# main_board.net
KiCad netlist of a schematic drawn in EAGLE
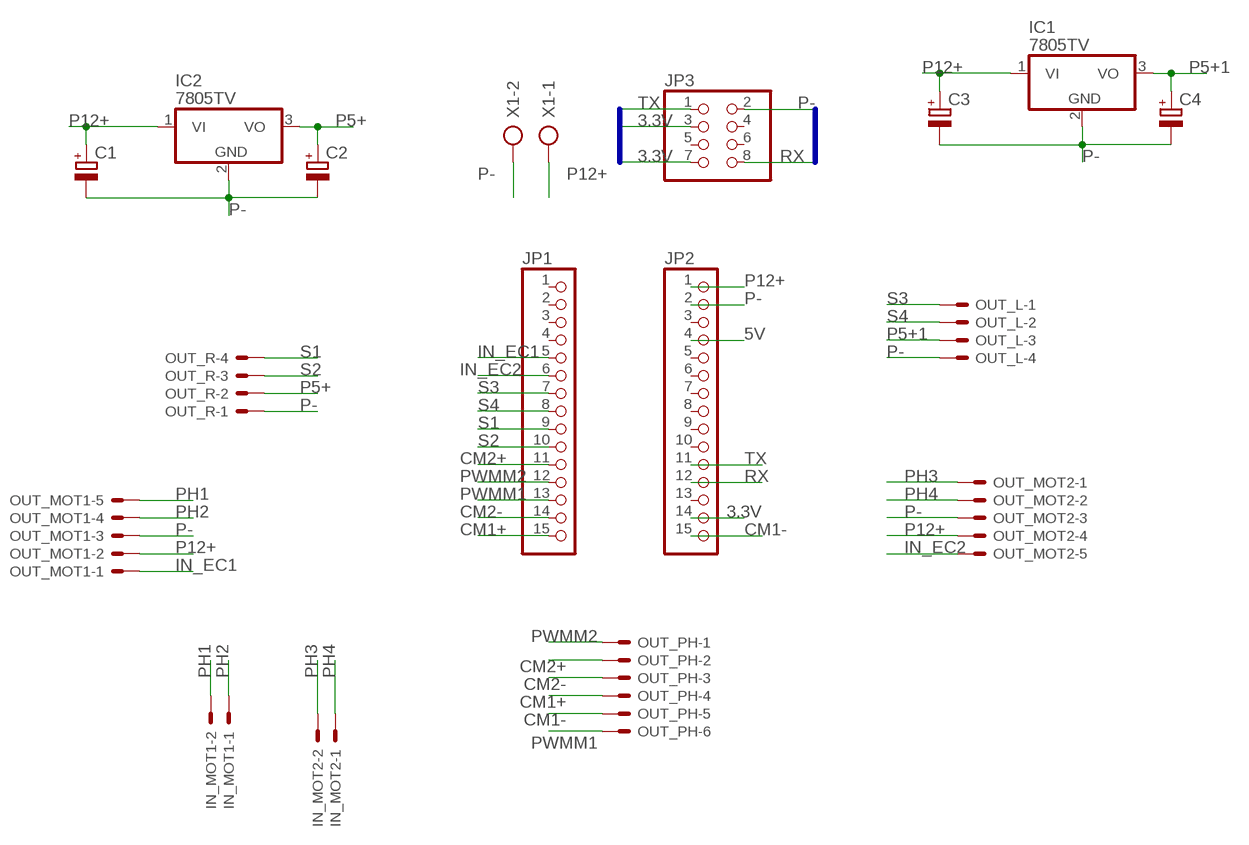
[diagram p0: schematic, sheet 1]

(export (version "E")
  (design (tool "Eeschema 10.0.6"))
  (components
    (comp (ref "C1")
      (value "CPOL-EUE3.5-10")
      (footprint "eagle-import:E3,5-10")
      (libsource (lib "eagle-import") (part "CPOL-EUE3.5-10"))
    )
    (comp (ref "C2")
      (value "CPOL-EUE3.5-10")
      (footprint "eagle-import:E3,5-10")
      (libsource (lib "eagle-import") (part "CPOL-EUE3.5-10"))
    )
    (comp (ref "C3")
      (value "CPOL-EUE3.5-10")
      (footprint "eagle-import:E3,5-10")
      (libsource (lib "eagle-import") (part "CPOL-EUE3.5-10"))
    )
    (comp (ref "C4")
      (value "CPOL-EUE3.5-10")
      (footprint "eagle-import:E3,5-10")
      (libsource (lib "eagle-import") (part "CPOL-EUE3.5-10"))
    )
    (comp (ref "IC1")
      (value "7805TV")
      (footprint "eagle-import:TO220V")
      (libsource (lib "eagle-import") (part "78TV05"))
    )
    (comp (ref "IC2")
      (value "7805TV")
      (footprint "eagle-import:TO220V")
      (libsource (lib "eagle-import") (part "78TV05"))
    )
    (comp (ref "IN_MOT1")
      (value "22-23-2021")
      (footprint "eagle-import:22-23-2021")
      (fields (field (name "MF") "MOLEX"))
      (libsource (lib "eagle-import") (part "22-23-2021"))
    )
    (comp (ref "IN_MOT2")
      (value "22-23-2021")
      (footprint "eagle-import:22-23-2021")
      (fields (field (name "MF") "MOLEX"))
      (libsource (lib "eagle-import") (part "22-23-2021"))
    )
    (comp (ref "JP1")
      (value "PINHD-1X15")
      (footprint "eagle-import:1X15")
      (libsource (lib "eagle-import") (part "PINHD-1X15"))
    )
    (comp (ref "JP2")
      (value "PINHD-1X15")
      (footprint "eagle-import:1X15")
      (libsource (lib "eagle-import") (part "PINHD-1X15"))
    )
    (comp (ref "JP3")
      (value "PINHD-2X4")
      (footprint "eagle-import:2X04")
      (libsource (lib "eagle-import") (part "PINHD-2X4"))
    )
    (comp (ref "OUT_L")
      (value "22-23-2041")
      (footprint "eagle-import:22-23-2041")
      (fields (field (name "MF") "MOLEX"))
      (libsource (lib "eagle-import") (part "22-23-2041"))
    )
    (comp (ref "OUT_MOT1")
      (value "22-23-2051")
      (footprint "eagle-import:22-23-2051")
      (fields (field (name "MF") "MOLEX"))
      (libsource (lib "eagle-import") (part "22-23-2051"))
    )
    (comp (ref "OUT_MOT2")
      (value "22-23-2051")
      (footprint "eagle-import:22-23-2051")
      (fields (field (name "MF") "MOLEX"))
      (libsource (lib "eagle-import") (part "22-23-2051"))
    )
    (comp (ref "OUT_PH")
      (value "22-23-2061")
      (footprint "eagle-import:22-23-2061")
      (fields (field (name "MF") "MOLEX"))
      (libsource (lib "eagle-import") (part "22-23-2061"))
    )
    (comp (ref "OUT_R")
      (value "22-23-2041")
      (footprint "eagle-import:22-23-2041")
      (fields (field (name "MF") "MOLEX"))
      (libsource (lib "eagle-import") (part "22-23-2041"))
    )
    (comp (ref "X1")
      (value "AK300/2")
      (footprint "eagle-import:AK300_2")
      (libsource (lib "eagle-import") (part "AK300/2"))
    )
  )
  (nets
    (net (code "1") (name "/3.3V") (class "Default")
      (node (ref "JP2") (pin "14") (pinfunction "14_14") (pintype "passive"))
      (node (ref "JP3") (pin "3") (pinfunction "3_3") (pintype "passive"))
      (node (ref "JP3") (pin "7") (pinfunction "7_7") (pintype "passive"))
    )
    (net (code "2") (name "/5V") (class "Default")
      (node (ref "JP2") (pin "4") (pinfunction "4_4") (pintype "passive"))
    )
    (net (code "3") (name "/CM1+") (class "Default")
      (node (ref "JP1") (pin "15") (pinfunction "15_15") (pintype "passive"))
      (node (ref "OUT_PH") (pin "4") (pinfunction "S_4") (pintype "passive"))
    )
    (net (code "4") (name "/CM1-") (class "Default")
      (node (ref "JP2") (pin "15") (pinfunction "15_15") (pintype "passive"))
      (node (ref "OUT_PH") (pin "5") (pinfunction "S_5") (pintype "passive"))
    )
    (net (code "5") (name "/CM2+") (class "Default")
      (node (ref "JP1") (pin "11") (pinfunction "11_11") (pintype "passive"))
      (node (ref "OUT_PH") (pin "2") (pinfunction "S_2") (pintype "passive"))
    )
    (net (code "6") (name "/CM2-") (class "Default")
      (node (ref "JP1") (pin "14") (pinfunction "14_14") (pintype "passive"))
      (node (ref "OUT_PH") (pin "3") (pinfunction "S_3") (pintype "passive"))
    )
    (net (code "7") (name "/IN_EC1") (class "Default")
      (node (ref "JP1") (pin "5") (pinfunction "5_5") (pintype "passive"))
      (node (ref "OUT_MOT1") (pin "1") (pinfunction "S_1") (pintype "passive"))
    )
    (net (code "8") (name "/IN_EC2") (class "Default")
      (node (ref "JP1") (pin "6") (pinfunction "6_6") (pintype "passive"))
      (node (ref "OUT_MOT2") (pin "5") (pinfunction "S_5") (pintype "passive"))
    )
    (net (code "9") (name "/P-") (class "Default")
      (node (ref "C1") (pin "-") (pinfunction "-_-") (pintype "passive"))
      (node (ref "C2") (pin "-") (pinfunction "-_-") (pintype "passive"))
      (node (ref "C3") (pin "-") (pinfunction "-_-") (pintype "passive"))
      (node (ref "C4") (pin "-") (pinfunction "-_-") (pintype "passive"))
      (node (ref "IC1") (pin "2") (pinfunction "GND_2") (pintype "passive"))
      (node (ref "IC2") (pin "2") (pinfunction "GND_2") (pintype "passive"))
      (node (ref "JP2") (pin "2") (pinfunction "2_2") (pintype "passive"))
      (node (ref "JP3") (pin "2") (pinfunction "2_2") (pintype "passive"))
      (node (ref "OUT_L") (pin "4") (pinfunction "S_4") (pintype "passive"))
      (node (ref "OUT_MOT1") (pin "3") (pinfunction "S_3") (pintype "passive"))
      (node (ref "OUT_MOT2") (pin "3") (pinfunction "S_3") (pintype "passive"))
      (node (ref "OUT_R") (pin "1") (pinfunction "S_1") (pintype "passive"))
      (node (ref "X1") (pin "2") (pinfunction "KL_2") (pintype "passive"))
    )
    (net (code "10") (name "/P5+") (class "Default")
      (node (ref "C2") (pin "+") (pinfunction "+_+") (pintype "passive"))
      (node (ref "IC2") (pin "3") (pinfunction "VO_3") (pintype "passive"))
      (node (ref "OUT_R") (pin "2") (pinfunction "S_2") (pintype "passive"))
    )
    (net (code "11") (name "/P5+1") (class "Default")
      (node (ref "C4") (pin "+") (pinfunction "+_+") (pintype "passive"))
      (node (ref "IC1") (pin "3") (pinfunction "VO_3") (pintype "passive"))
      (node (ref "OUT_L") (pin "3") (pinfunction "S_3") (pintype "passive"))
    )
    (net (code "12") (name "/P12+") (class "Default")
      (node (ref "C1") (pin "+") (pinfunction "+_+") (pintype "passive"))
      (node (ref "C3") (pin "+") (pinfunction "+_+") (pintype "passive"))
      (node (ref "IC1") (pin "1") (pinfunction "VI_1") (pintype "input"))
      (node (ref "IC2") (pin "1") (pinfunction "VI_1") (pintype "input"))
      (node (ref "JP2") (pin "1") (pinfunction "1_1") (pintype "passive"))
      (node (ref "OUT_MOT1") (pin "2") (pinfunction "S_2") (pintype "passive"))
      (node (ref "OUT_MOT2") (pin "4") (pinfunction "S_4") (pintype "passive"))
      (node (ref "X1") (pin "1") (pinfunction "KL_1") (pintype "passive"))
    )
    (net (code "13") (name "/PH1") (class "Default")
      (node (ref "IN_MOT1") (pin "2") (pinfunction "S_2") (pintype "passive"))
      (node (ref "OUT_MOT1") (pin "5") (pinfunction "S_5") (pintype "passive"))
    )
    (net (code "14") (name "/PH2") (class "Default")
      (node (ref "IN_MOT1") (pin "1") (pinfunction "S_1") (pintype "passive"))
      (node (ref "OUT_MOT1") (pin "4") (pinfunction "S_4") (pintype "passive"))
    )
    (net (code "15") (name "/PH3") (class "Default")
      (node (ref "IN_MOT2") (pin "2") (pinfunction "S_2") (pintype "passive"))
      (node (ref "OUT_MOT2") (pin "1") (pinfunction "S_1") (pintype "passive"))
    )
    (net (code "16") (name "/PH4") (class "Default")
      (node (ref "IN_MOT2") (pin "1") (pinfunction "S_1") (pintype "passive"))
      (node (ref "OUT_MOT2") (pin "2") (pinfunction "S_2") (pintype "passive"))
    )
    (net (code "17") (name "/PWMM1") (class "Default")
      (node (ref "JP1") (pin "13") (pinfunction "13_13") (pintype "passive"))
      (node (ref "OUT_PH") (pin "6") (pinfunction "S_6") (pintype "passive"))
    )
    (net (code "18") (name "/PWMM2") (class "Default")
      (node (ref "JP1") (pin "12") (pinfunction "12_12") (pintype "passive"))
      (node (ref "OUT_PH") (pin "1") (pinfunction "S_1") (pintype "passive"))
    )
    (net (code "19") (name "/RX") (class "Default")
      (node (ref "JP2") (pin "12") (pinfunction "12_12") (pintype "passive"))
      (node (ref "JP3") (pin "8") (pinfunction "8_8") (pintype "passive"))
    )
    (net (code "20") (name "/S1") (class "Default")
      (node (ref "JP1") (pin "9") (pinfunction "9_9") (pintype "passive"))
      (node (ref "OUT_R") (pin "4") (pinfunction "S_4") (pintype "passive"))
    )
    (net (code "21") (name "/S2") (class "Default")
      (node (ref "JP1") (pin "10") (pinfunction "10_10") (pintype "passive"))
      (node (ref "OUT_R") (pin "3") (pinfunction "S_3") (pintype "passive"))
    )
    (net (code "22") (name "/S3") (class "Default")
      (node (ref "JP1") (pin "7") (pinfunction "7_7") (pintype "passive"))
      (node (ref "OUT_L") (pin "1") (pinfunction "S_1") (pintype "passive"))
    )
    (net (code "23") (name "/S4") (class "Default")
      (node (ref "JP1") (pin "8") (pinfunction "8_8") (pintype "passive"))
      (node (ref "OUT_L") (pin "2") (pinfunction "S_2") (pintype "passive"))
    )
    (net (code "24") (name "/TX") (class "Default")
      (node (ref "JP2") (pin "11") (pinfunction "11_11") (pintype "passive"))
      (node (ref "JP3") (pin "1") (pinfunction "1_1") (pintype "passive"))
    )
    (net (code "25") (name "unconnected-(JP1-Pad1)") (class "Default")
      (node (ref "JP1") (pin "1") (pinfunction "1_1") (pintype "passive"))
    )
    (net (code "26") (name "unconnected-(JP1-Pad2)") (class "Default")
      (node (ref "JP1") (pin "2") (pinfunction "2_2") (pintype "passive"))
    )
    (net (code "27") (name "unconnected-(JP1-Pad3)") (class "Default")
      (node (ref "JP1") (pin "3") (pinfunction "3_3") (pintype "passive"))
    )
    (net (code "28") (name "unconnected-(JP1-Pad4)") (class "Default")
      (node (ref "JP1") (pin "4") (pinfunction "4_4") (pintype "passive"))
    )
    (net (code "29") (name "unconnected-(JP2-Pad3)") (class "Default")
      (node (ref "JP2") (pin "3") (pinfunction "3_3") (pintype "passive"))
    )
    (net (code "30") (name "unconnected-(JP2-Pad5)") (class "Default")
      (node (ref "JP2") (pin "5") (pinfunction "5_5") (pintype "passive"))
    )
    (net (code "31") (name "unconnected-(JP2-Pad6)") (class "Default")
      (node (ref "JP2") (pin "6") (pinfunction "6_6") (pintype "passive"))
    )
    (net (code "32") (name "unconnected-(JP2-Pad7)") (class "Default")
      (node (ref "JP2") (pin "7") (pinfunction "7_7") (pintype "passive"))
    )
    (net (code "33") (name "unconnected-(JP2-Pad8)") (class "Default")
      (node (ref "JP2") (pin "8") (pinfunction "8_8") (pintype "passive"))
    )
    (net (code "34") (name "unconnected-(JP2-Pad9)") (class "Default")
      (node (ref "JP2") (pin "9") (pinfunction "9_9") (pintype "passive"))
    )
    (net (code "35") (name "unconnected-(JP2-Pad10)") (class "Default")
      (node (ref "JP2") (pin "10") (pinfunction "10_10") (pintype "passive"))
    )
    (net (code "36") (name "unconnected-(JP2-Pad13)") (class "Default")
      (node (ref "JP2") (pin "13") (pinfunction "13_13") (pintype "passive"))
    )
    (net (code "37") (name "unconnected-(JP3-Pad4)") (class "Default")
      (node (ref "JP3") (pin "4") (pinfunction "4_4") (pintype "passive"))
    )
    (net (code "38") (name "unconnected-(JP3-Pad5)") (class "Default")
      (node (ref "JP3") (pin "5") (pinfunction "5_5") (pintype "passive"))
    )
    (net (code "39") (name "unconnected-(JP3-Pad6)") (class "Default")
      (node (ref "JP3") (pin "6") (pinfunction "6_6") (pintype "passive"))
    )
  )
)
